# 4x4-programmable-keypad.net
KiCad netlist of a schematic drawn in EAGLE
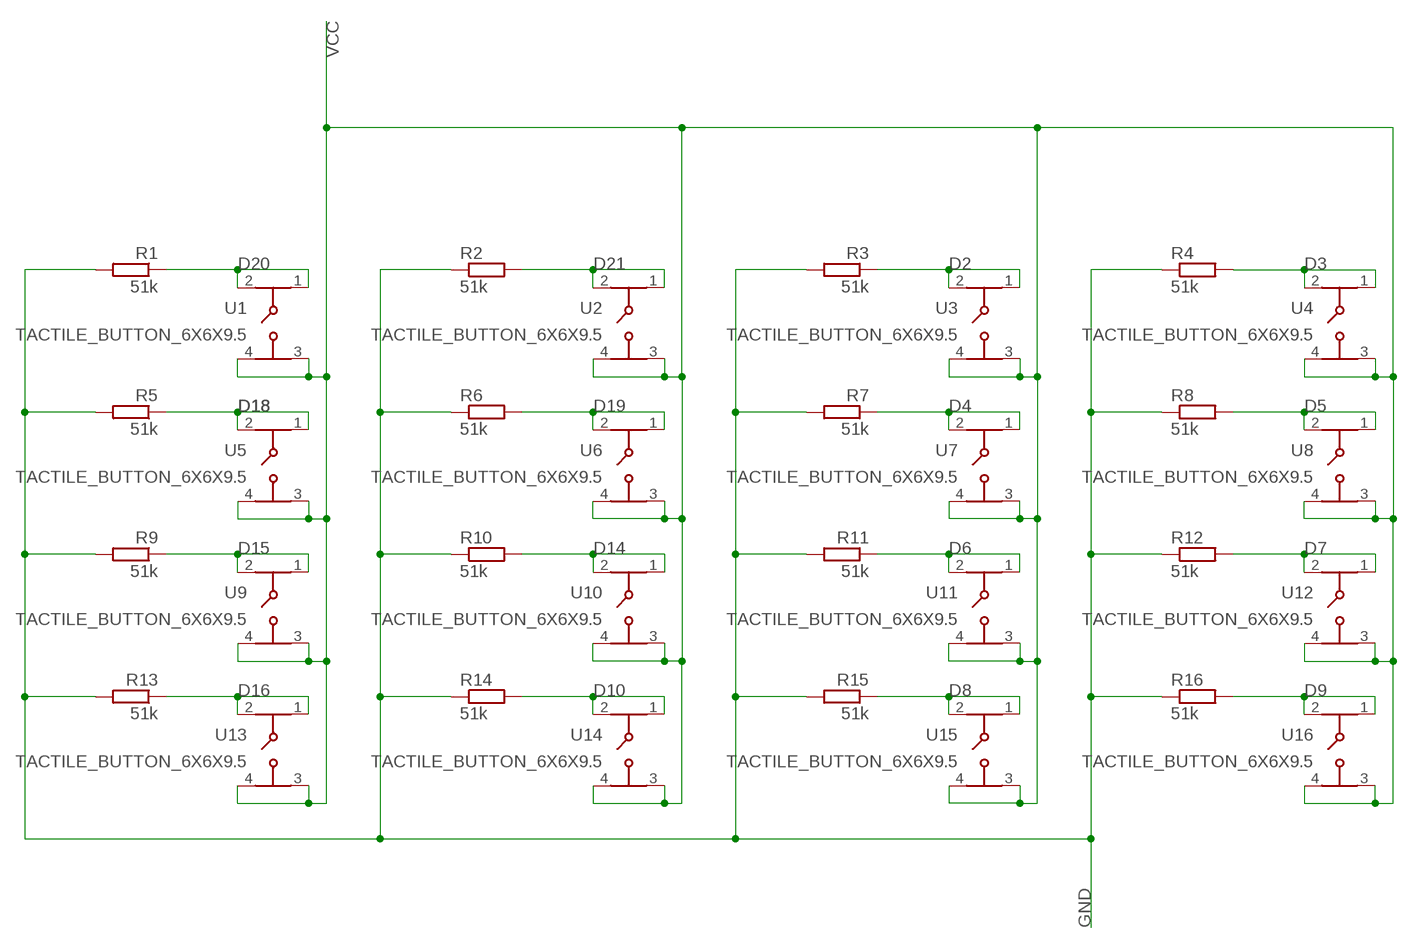
[diagram p0: schematic, sheet 1]
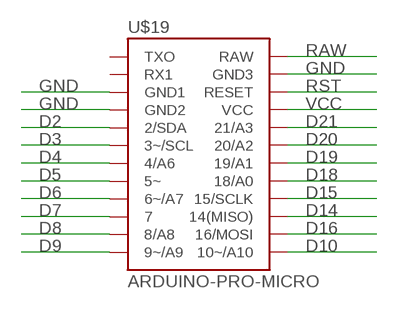
[diagram p1: schematic, sheet 2]

(export (version "E")
  (design (tool "Eeschema 10.0.6"))
  (components
    (comp (ref "R1")
      (value "51k")
      (footprint "eagle-import:R0603")
      (libsource (lib "eagle-import") (part "R-EU_R0603"))
    )
    (comp (ref "R2")
      (value "51k")
      (footprint "eagle-import:R0603")
      (libsource (lib "eagle-import") (part "R-EU_R0603"))
    )
    (comp (ref "R3")
      (value "51k")
      (footprint "eagle-import:R0603")
      (libsource (lib "eagle-import") (part "R-EU_R0603"))
    )
    (comp (ref "R4")
      (value "51k")
      (footprint "eagle-import:R0603")
      (libsource (lib "eagle-import") (part "R-EU_R0603"))
    )
    (comp (ref "R5")
      (value "51k")
      (footprint "eagle-import:R0603")
      (libsource (lib "eagle-import") (part "R-EU_R0603"))
    )
    (comp (ref "R6")
      (value "51k")
      (footprint "eagle-import:R0603")
      (libsource (lib "eagle-import") (part "R-EU_R0603"))
    )
    (comp (ref "R7")
      (value "51k")
      (footprint "eagle-import:R0603")
      (libsource (lib "eagle-import") (part "R-EU_R0603"))
    )
    (comp (ref "R8")
      (value "51k")
      (footprint "eagle-import:R0603")
      (libsource (lib "eagle-import") (part "R-EU_R0603"))
    )
    (comp (ref "R9")
      (value "51k")
      (footprint "eagle-import:R0603")
      (libsource (lib "eagle-import") (part "R-EU_R0603"))
    )
    (comp (ref "R10")
      (value "51k")
      (footprint "eagle-import:R0603")
      (libsource (lib "eagle-import") (part "R-EU_R0603"))
    )
    (comp (ref "R11")
      (value "51k")
      (footprint "eagle-import:R0603")
      (libsource (lib "eagle-import") (part "R-EU_R0603"))
    )
    (comp (ref "R12")
      (value "51k")
      (footprint "eagle-import:R0603")
      (libsource (lib "eagle-import") (part "R-EU_R0603"))
    )
    (comp (ref "R13")
      (value "51k")
      (footprint "eagle-import:R0603")
      (libsource (lib "eagle-import") (part "R-EU_R0603"))
    )
    (comp (ref "R14")
      (value "51k")
      (footprint "eagle-import:R0603")
      (libsource (lib "eagle-import") (part "R-EU_R0603"))
    )
    (comp (ref "R15")
      (value "51k")
      (footprint "eagle-import:R0603")
      (libsource (lib "eagle-import") (part "R-EU_R0603"))
    )
    (comp (ref "R16")
      (value "51k")
      (footprint "eagle-import:R0603")
      (libsource (lib "eagle-import") (part "R-EU_R0603"))
    )
    (comp (ref "U1")
      (value "TACTILE_BUTTON_6X6X9.5")
      (footprint "eagle-import:TACTILE_SWITCH_PTH_6.0MM")
      (libsource (lib "eagle-import") (part "TACTILE_BUTTON_6X6X9.5"))
    )
    (comp (ref "U2")
      (value "TACTILE_BUTTON_6X6X9.5")
      (footprint "eagle-import:TACTILE_SWITCH_PTH_6.0MM")
      (libsource (lib "eagle-import") (part "TACTILE_BUTTON_6X6X9.5"))
    )
    (comp (ref "U3")
      (value "TACTILE_BUTTON_6X6X9.5")
      (footprint "eagle-import:TACTILE_SWITCH_PTH_6.0MM")
      (libsource (lib "eagle-import") (part "TACTILE_BUTTON_6X6X9.5"))
    )
    (comp (ref "U4")
      (value "TACTILE_BUTTON_6X6X9.5")
      (footprint "eagle-import:TACTILE_SWITCH_PTH_6.0MM")
      (libsource (lib "eagle-import") (part "TACTILE_BUTTON_6X6X9.5"))
    )
    (comp (ref "U5")
      (value "TACTILE_BUTTON_6X6X9.5")
      (footprint "eagle-import:TACTILE_SWITCH_PTH_6.0MM")
      (libsource (lib "eagle-import") (part "TACTILE_BUTTON_6X6X9.5"))
    )
    (comp (ref "U6")
      (value "TACTILE_BUTTON_6X6X9.5")
      (footprint "eagle-import:TACTILE_SWITCH_PTH_6.0MM")
      (libsource (lib "eagle-import") (part "TACTILE_BUTTON_6X6X9.5"))
    )
    (comp (ref "U7")
      (value "TACTILE_BUTTON_6X6X9.5")
      (footprint "eagle-import:TACTILE_SWITCH_PTH_6.0MM")
      (libsource (lib "eagle-import") (part "TACTILE_BUTTON_6X6X9.5"))
    )
    (comp (ref "U8")
      (value "TACTILE_BUTTON_6X6X9.5")
      (footprint "eagle-import:TACTILE_SWITCH_PTH_6.0MM")
      (libsource (lib "eagle-import") (part "TACTILE_BUTTON_6X6X9.5"))
    )
    (comp (ref "U9")
      (value "TACTILE_BUTTON_6X6X9.5")
      (footprint "eagle-import:TACTILE_SWITCH_PTH_6.0MM")
      (libsource (lib "eagle-import") (part "TACTILE_BUTTON_6X6X9.5"))
    )
    (comp (ref "U10")
      (value "TACTILE_BUTTON_6X6X9.5")
      (footprint "eagle-import:TACTILE_SWITCH_PTH_6.0MM")
      (libsource (lib "eagle-import") (part "TACTILE_BUTTON_6X6X9.5"))
    )
    (comp (ref "U11")
      (value "TACTILE_BUTTON_6X6X9.5")
      (footprint "eagle-import:TACTILE_SWITCH_PTH_6.0MM")
      (libsource (lib "eagle-import") (part "TACTILE_BUTTON_6X6X9.5"))
    )
    (comp (ref "U12")
      (value "TACTILE_BUTTON_6X6X9.5")
      (footprint "eagle-import:TACTILE_SWITCH_PTH_6.0MM")
      (libsource (lib "eagle-import") (part "TACTILE_BUTTON_6X6X9.5"))
    )
    (comp (ref "U13")
      (value "TACTILE_BUTTON_6X6X9.5")
      (footprint "eagle-import:TACTILE_SWITCH_PTH_6.0MM")
      (libsource (lib "eagle-import") (part "TACTILE_BUTTON_6X6X9.5"))
    )
    (comp (ref "U14")
      (value "TACTILE_BUTTON_6X6X9.5")
      (footprint "eagle-import:TACTILE_SWITCH_PTH_6.0MM")
      (libsource (lib "eagle-import") (part "TACTILE_BUTTON_6X6X9.5"))
    )
    (comp (ref "U15")
      (value "TACTILE_BUTTON_6X6X9.5")
      (footprint "eagle-import:TACTILE_SWITCH_PTH_6.0MM")
      (libsource (lib "eagle-import") (part "TACTILE_BUTTON_6X6X9.5"))
    )
    (comp (ref "U16")
      (value "TACTILE_BUTTON_6X6X9.5")
      (footprint "eagle-import:TACTILE_SWITCH_PTH_6.0MM")
      (libsource (lib "eagle-import") (part "TACTILE_BUTTON_6X6X9.5"))
    )
    (comp (ref "U$19")
      (value "ARDUINO-PRO-MICRO")
      (footprint "eagle-import:SPARKFUN_PRO_MICRO")
      (libsource (lib "eagle-import") (part "ARDUINO-PRO-MICRO"))
    )
  )
  (nets
    (net (code "1") (name "D2") (class "Default")
      (node (ref "R3") (pin "1") (pinfunction "1_1") (pintype "passive"))
      (node (ref "U$19") (pin "2/SDA") (pinfunction "2/SDA_2/SDA") (pintype "bidirectional"))
      (node (ref "U3") (pin "1") (pinfunction "1_1") (pintype "passive"))
      (node (ref "U3") (pin "2") (pinfunction "3_2") (pintype "passive"))
    )
    (net (code "2") (name "D3") (class "Default")
      (node (ref "R4") (pin "2") (pinfunction "2_2") (pintype "passive"))
      (node (ref "U$19") (pin "3~/SCL") (pinfunction "3~{/SCL}_3~/SCL") (pintype "bidirectional"))
      (node (ref "U4") (pin "1") (pinfunction "1_1") (pintype "passive"))
      (node (ref "U4") (pin "2") (pinfunction "3_2") (pintype "passive"))
    )
    (net (code "3") (name "D4") (class "Default")
      (node (ref "R7") (pin "1") (pinfunction "1_1") (pintype "passive"))
      (node (ref "U$19") (pin "4/A6") (pinfunction "4/A6_4/A6") (pintype "bidirectional"))
      (node (ref "U7") (pin "1") (pinfunction "1_1") (pintype "passive"))
      (node (ref "U7") (pin "2") (pinfunction "3_2") (pintype "passive"))
    )
    (net (code "4") (name "D5") (class "Default")
      (node (ref "R8") (pin "2") (pinfunction "2_2") (pintype "passive"))
      (node (ref "U$19") (pin "5~") (pinfunction "5~{}_5~") (pintype "bidirectional"))
      (node (ref "U8") (pin "1") (pinfunction "1_1") (pintype "passive"))
      (node (ref "U8") (pin "2") (pinfunction "3_2") (pintype "passive"))
    )
    (net (code "5") (name "D6") (class "Default")
      (node (ref "R11") (pin "1") (pinfunction "1_1") (pintype "passive"))
      (node (ref "U$19") (pin "6~/A7") (pinfunction "6~{/A7}_6~/A7") (pintype "bidirectional"))
      (node (ref "U11") (pin "1") (pinfunction "1_1") (pintype "passive"))
      (node (ref "U11") (pin "2") (pinfunction "3_2") (pintype "passive"))
    )
    (net (code "6") (name "D7") (class "Default")
      (node (ref "R12") (pin "2") (pinfunction "2_2") (pintype "passive"))
      (node (ref "U$19") (pin "7") (pinfunction "7_7") (pintype "bidirectional"))
      (node (ref "U12") (pin "1") (pinfunction "1_1") (pintype "passive"))
      (node (ref "U12") (pin "2") (pinfunction "3_2") (pintype "passive"))
    )
    (net (code "7") (name "D8") (class "Default")
      (node (ref "R15") (pin "1") (pinfunction "1_1") (pintype "passive"))
      (node (ref "U$19") (pin "8/A8") (pinfunction "8/A8_8/A8") (pintype "bidirectional"))
      (node (ref "U15") (pin "1") (pinfunction "1_1") (pintype "passive"))
      (node (ref "U15") (pin "2") (pinfunction "3_2") (pintype "passive"))
    )
    (net (code "8") (name "D9") (class "Default")
      (node (ref "R16") (pin "2") (pinfunction "2_2") (pintype "passive"))
      (node (ref "U$19") (pin "9~/A9") (pinfunction "9~{/A9}_9~/A9") (pintype "bidirectional"))
      (node (ref "U16") (pin "1") (pinfunction "1_1") (pintype "passive"))
      (node (ref "U16") (pin "2") (pinfunction "3_2") (pintype "passive"))
    )
    (net (code "9") (name "D10") (class "Default")
      (node (ref "R14") (pin "2") (pinfunction "2_2") (pintype "passive"))
      (node (ref "U$19") (pin "10~/A10") (pinfunction "10~{/A10}_10~/A10") (pintype "bidirectional"))
      (node (ref "U14") (pin "1") (pinfunction "1_1") (pintype "passive"))
      (node (ref "U14") (pin "2") (pinfunction "3_2") (pintype "passive"))
    )
    (net (code "10") (name "D14") (class "Default")
      (node (ref "R10") (pin "2") (pinfunction "2_2") (pintype "passive"))
      (node (ref "U$19") (pin "14/MISO") (pinfunction "14(MISO)_14/MISO") (pintype "bidirectional"))
      (node (ref "U10") (pin "1") (pinfunction "1_1") (pintype "passive"))
      (node (ref "U10") (pin "2") (pinfunction "3_2") (pintype "passive"))
    )
    (net (code "11") (name "D15") (class "Default")
      (node (ref "R9") (pin "1") (pinfunction "1_1") (pintype "passive"))
      (node (ref "U$19") (pin "15/SCLK") (pinfunction "15/SCLK_15/SCLK") (pintype "bidirectional"))
      (node (ref "U9") (pin "1") (pinfunction "1_1") (pintype "passive"))
      (node (ref "U9") (pin "2") (pinfunction "3_2") (pintype "passive"))
    )
    (net (code "12") (name "D16") (class "Default")
      (node (ref "R13") (pin "1") (pinfunction "1_1") (pintype "passive"))
      (node (ref "U$19") (pin "16/MOSI") (pinfunction "16/MOSI_16/MOSI") (pintype "bidirectional"))
      (node (ref "U13") (pin "1") (pinfunction "1_1") (pintype "passive"))
      (node (ref "U13") (pin "2") (pinfunction "3_2") (pintype "passive"))
    )
    (net (code "13") (name "D18") (class "Default")
      (node (ref "R5") (pin "1") (pinfunction "1_1") (pintype "passive"))
      (node (ref "U$19") (pin "18/A0") (pinfunction "18/A0_18/A0") (pintype "bidirectional"))
      (node (ref "U5") (pin "1") (pinfunction "1_1") (pintype "passive"))
      (node (ref "U5") (pin "2") (pinfunction "3_2") (pintype "passive"))
    )
    (net (code "14") (name "D19") (class "Default")
      (node (ref "R6") (pin "2") (pinfunction "2_2") (pintype "passive"))
      (node (ref "U$19") (pin "19/A1") (pinfunction "19/A1_19/A1") (pintype "bidirectional"))
      (node (ref "U6") (pin "1") (pinfunction "1_1") (pintype "passive"))
      (node (ref "U6") (pin "2") (pinfunction "3_2") (pintype "passive"))
    )
    (net (code "15") (name "D20") (class "Default")
      (node (ref "R1") (pin "1") (pinfunction "1_1") (pintype "passive"))
      (node (ref "U$19") (pin "20/A2") (pinfunction "20/A2_20/A2") (pintype "bidirectional"))
      (node (ref "U1") (pin "1") (pinfunction "1_1") (pintype "passive"))
      (node (ref "U1") (pin "2") (pinfunction "3_2") (pintype "passive"))
    )
    (net (code "16") (name "D21") (class "Default")
      (node (ref "R2") (pin "2") (pinfunction "2_2") (pintype "passive"))
      (node (ref "U$19") (pin "21/A3") (pinfunction "21/A3_21/A3") (pintype "bidirectional"))
      (node (ref "U2") (pin "1") (pinfunction "1_1") (pintype "passive"))
      (node (ref "U2") (pin "2") (pinfunction "3_2") (pintype "passive"))
    )
    (net (code "17") (name "GND") (class "Default")
      (node (ref "R1") (pin "2") (pinfunction "2_2") (pintype "passive"))
      (node (ref "R10") (pin "1") (pinfunction "1_1") (pintype "passive"))
      (node (ref "R11") (pin "2") (pinfunction "2_2") (pintype "passive"))
      (node (ref "R12") (pin "1") (pinfunction "1_1") (pintype "passive"))
      (node (ref "R13") (pin "2") (pinfunction "2_2") (pintype "passive"))
      (node (ref "R14") (pin "1") (pinfunction "1_1") (pintype "passive"))
      (node (ref "R15") (pin "2") (pinfunction "2_2") (pintype "passive"))
      (node (ref "R16") (pin "1") (pinfunction "1_1") (pintype "passive"))
      (node (ref "R2") (pin "1") (pinfunction "1_1") (pintype "passive"))
      (node (ref "R3") (pin "2") (pinfunction "2_2") (pintype "passive"))
      (node (ref "R4") (pin "1") (pinfunction "1_1") (pintype "passive"))
      (node (ref "R5") (pin "2") (pinfunction "2_2") (pintype "passive"))
      (node (ref "R6") (pin "1") (pinfunction "1_1") (pintype "passive"))
      (node (ref "R7") (pin "2") (pinfunction "2_2") (pintype "passive"))
      (node (ref "R8") (pin "1") (pinfunction "1_1") (pintype "passive"))
      (node (ref "R9") (pin "2") (pinfunction "2_2") (pintype "passive"))
      (node (ref "U$19") (pin "GND1") (pinfunction "GND1_GND1") (pintype "power_in"))
      (node (ref "U$19") (pin "GND2") (pinfunction "GND2_GND2") (pintype "power_in"))
      (node (ref "U$19") (pin "GND3") (pinfunction "GND3_GND3") (pintype "power_in"))
    )
    (net (code "18") (name "RAW") (class "Default")
      (node (ref "U$19") (pin "RAW") (pinfunction "RAW_RAW") (pintype "power_in"))
    )
    (net (code "19") (name "RST") (class "Default")
      (node (ref "U$19") (pin "RST") (pinfunction "RESET_RST") (pintype "bidirectional"))
    )
    (net (code "20") (name "VCC") (class "Default")
      (node (ref "U$19") (pin "VCC") (pinfunction "VCC_VCC") (pintype "power_in"))
      (node (ref "U1") (pin "3") (pinfunction "2_3") (pintype "passive"))
      (node (ref "U1") (pin "4") (pinfunction "4_4") (pintype "passive"))
      (node (ref "U10") (pin "3") (pinfunction "2_3") (pintype "passive"))
      (node (ref "U10") (pin "4") (pinfunction "4_4") (pintype "passive"))
      (node (ref "U11") (pin "3") (pinfunction "2_3") (pintype "passive"))
      (node (ref "U11") (pin "4") (pinfunction "4_4") (pintype "passive"))
      (node (ref "U12") (pin "3") (pinfunction "2_3") (pintype "passive"))
      (node (ref "U12") (pin "4") (pinfunction "4_4") (pintype "passive"))
      (node (ref "U13") (pin "3") (pinfunction "2_3") (pintype "passive"))
      (node (ref "U13") (pin "4") (pinfunction "4_4") (pintype "passive"))
      (node (ref "U14") (pin "3") (pinfunction "2_3") (pintype "passive"))
      (node (ref "U14") (pin "4") (pinfunction "4_4") (pintype "passive"))
      (node (ref "U15") (pin "3") (pinfunction "2_3") (pintype "passive"))
      (node (ref "U15") (pin "4") (pinfunction "4_4") (pintype "passive"))
      (node (ref "U16") (pin "3") (pinfunction "2_3") (pintype "passive"))
      (node (ref "U16") (pin "4") (pinfunction "4_4") (pintype "passive"))
      (node (ref "U2") (pin "3") (pinfunction "2_3") (pintype "passive"))
      (node (ref "U2") (pin "4") (pinfunction "4_4") (pintype "passive"))
      (node (ref "U3") (pin "3") (pinfunction "2_3") (pintype "passive"))
      (node (ref "U3") (pin "4") (pinfunction "4_4") (pintype "passive"))
      (node (ref "U4") (pin "3") (pinfunction "2_3") (pintype "passive"))
      (node (ref "U4") (pin "4") (pinfunction "4_4") (pintype "passive"))
      (node (ref "U5") (pin "3") (pinfunction "2_3") (pintype "passive"))
      (node (ref "U5") (pin "4") (pinfunction "4_4") (pintype "passive"))
      (node (ref "U6") (pin "3") (pinfunction "2_3") (pintype "passive"))
      (node (ref "U6") (pin "4") (pinfunction "4_4") (pintype "passive"))
      (node (ref "U7") (pin "3") (pinfunction "2_3") (pintype "passive"))
      (node (ref "U7") (pin "4") (pinfunction "4_4") (pintype "passive"))
      (node (ref "U8") (pin "3") (pinfunction "2_3") (pintype "passive"))
      (node (ref "U8") (pin "4") (pinfunction "4_4") (pintype "passive"))
      (node (ref "U9") (pin "3") (pinfunction "2_3") (pintype "passive"))
      (node (ref "U9") (pin "4") (pinfunction "4_4") (pintype "passive"))
    )
    (net (code "21") (name "unconnected-(U$19-PadRX1)") (class "Default")
      (node (ref "U$19") (pin "RX1") (pinfunction "RX1_RX1") (pintype "bidirectional"))
    )
    (net (code "22") (name "unconnected-(U$19-TXO-PadTX0)") (class "Default")
      (node (ref "U$19") (pin "TX0") (pinfunction "TXO_TX0") (pintype "bidirectional"))
    )
  )
)
